# SCH_halloween-prokect_2024-10-07.net
KiCad netlist of a schematic drawn in EasyEDA
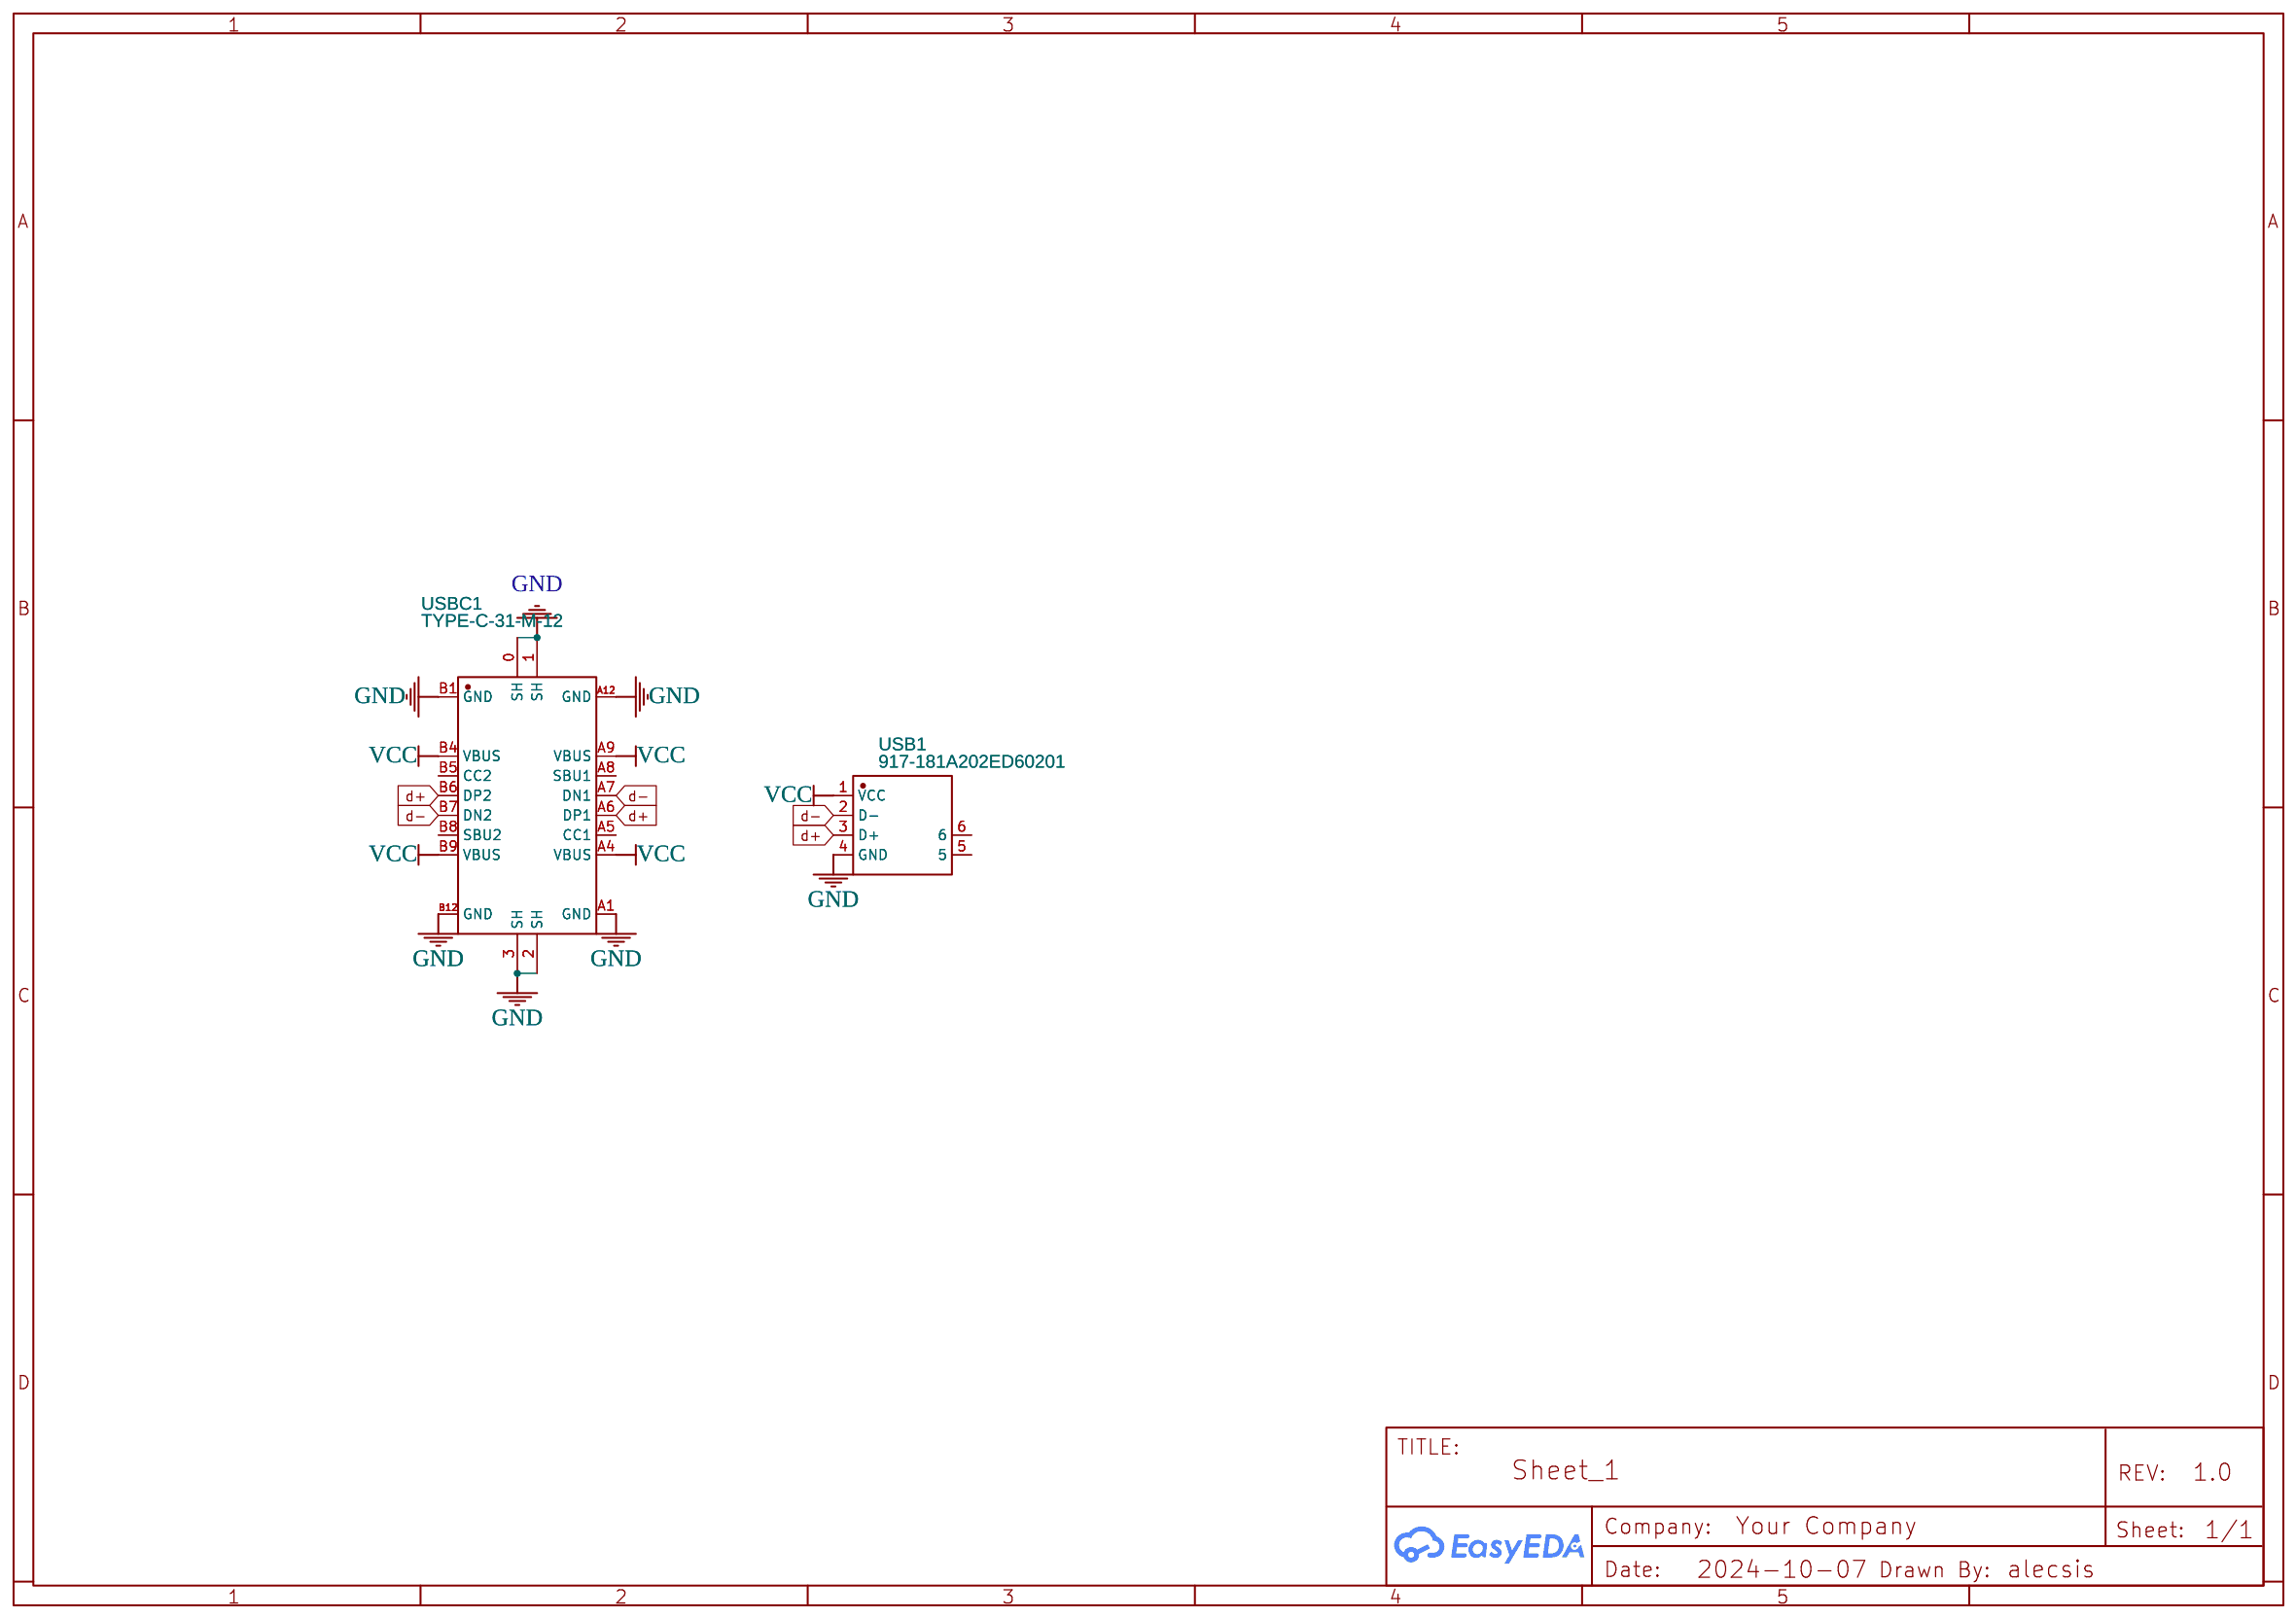
[diagram p0: schematic sheet]

(export (version "E")
  (design (tool "Eeschema 10.0.6"))
  (components
    (comp (ref "USB1")
      (value "917-181A202ED60201")
      (fields (field (name "Manufacturer") "精拓金"))
      (libsource (lib "") (part "917-181A202ED60201"))
    )
    (comp (ref "USBC1")
      (value "TYPE-C-31-M-12")
      (fields (field (name "Manufacturer") "韩国韩荣"))
      (libsource (lib "") (part "TYPE-C-31-M-12"))
    )
  )
  (nets
    (net (code "1") (name "GND") (class "Default")
      (node (ref "USB1") (pin "4") (pinfunction "GND_4") (pintype "unspecified"))
      (node (ref "USBC1") (pin "0") (pinfunction "SH_0") (pintype "unspecified"))
      (node (ref "USBC1") (pin "1") (pinfunction "SH_1") (pintype "unspecified"))
      (node (ref "USBC1") (pin "2") (pinfunction "SH_2") (pintype "unspecified"))
      (node (ref "USBC1") (pin "3") (pinfunction "SH_3") (pintype "unspecified"))
      (node (ref "USBC1") (pin "A1") (pinfunction "GND_A1") (pintype "unspecified"))
      (node (ref "USBC1") (pin "A12") (pinfunction "GND_A12") (pintype "unspecified"))
      (node (ref "USBC1") (pin "B1") (pinfunction "GND_B1") (pintype "unspecified"))
      (node (ref "USBC1") (pin "B12") (pinfunction "GND_B12") (pintype "unspecified"))
    )
    (net (code "2") (name "VCC") (class "Default")
      (node (ref "USB1") (pin "1") (pinfunction "VCC_1") (pintype "unspecified"))
      (node (ref "USBC1") (pin "A4") (pinfunction "VBUS_A4") (pintype "unspecified"))
      (node (ref "USBC1") (pin "A9") (pinfunction "VBUS_A9") (pintype "unspecified"))
      (node (ref "USBC1") (pin "B4") (pinfunction "VBUS_B4") (pintype "unspecified"))
      (node (ref "USBC1") (pin "B9") (pinfunction "VBUS_B9") (pintype "unspecified"))
    )
    (net (code "3") (name "d+") (class "Default")
      (node (ref "USB1") (pin "3") (pinfunction "D+_3") (pintype "unspecified"))
      (node (ref "USBC1") (pin "A6") (pinfunction "DP1_A6") (pintype "unspecified"))
      (node (ref "USBC1") (pin "B6") (pinfunction "DP2_B6") (pintype "unspecified"))
    )
    (net (code "4") (name "d-") (class "Default")
      (node (ref "USB1") (pin "2") (pinfunction "D-_2") (pintype "unspecified"))
      (node (ref "USBC1") (pin "A7") (pinfunction "DN1_A7") (pintype "unspecified"))
      (node (ref "USBC1") (pin "B7") (pinfunction "DN2_B7") (pintype "unspecified"))
    )
    (net (code "5") (name "unconnected-(USB1-Pad5)") (class "Default")
      (node (ref "USB1") (pin "5") (pinfunction "5_5") (pintype "unspecified"))
    )
    (net (code "6") (name "unconnected-(USB1-Pad6)") (class "Default")
      (node (ref "USB1") (pin "6") (pinfunction "6_6") (pintype "unspecified"))
    )
    (net (code "7") (name "unconnected-(USBC1-CC1-PadA5)") (class "Default")
      (node (ref "USBC1") (pin "A5") (pinfunction "CC1_A5") (pintype "unspecified"))
    )
    (net (code "8") (name "unconnected-(USBC1-CC2-PadB5)") (class "Default")
      (node (ref "USBC1") (pin "B5") (pinfunction "CC2_B5") (pintype "unspecified"))
    )
    (net (code "9") (name "unconnected-(USBC1-SBU1-PadA8)") (class "Default")
      (node (ref "USBC1") (pin "A8") (pinfunction "SBU1_A8") (pintype "unspecified"))
    )
    (net (code "10") (name "unconnected-(USBC1-SBU2-PadB8)") (class "Default")
      (node (ref "USBC1") (pin "B8") (pinfunction "SBU2_B8") (pintype "unspecified"))
    )
  )
)
